# AC_DCConvertor_v2.net
KiCad netlist of a schematic drawn in Altium Designer
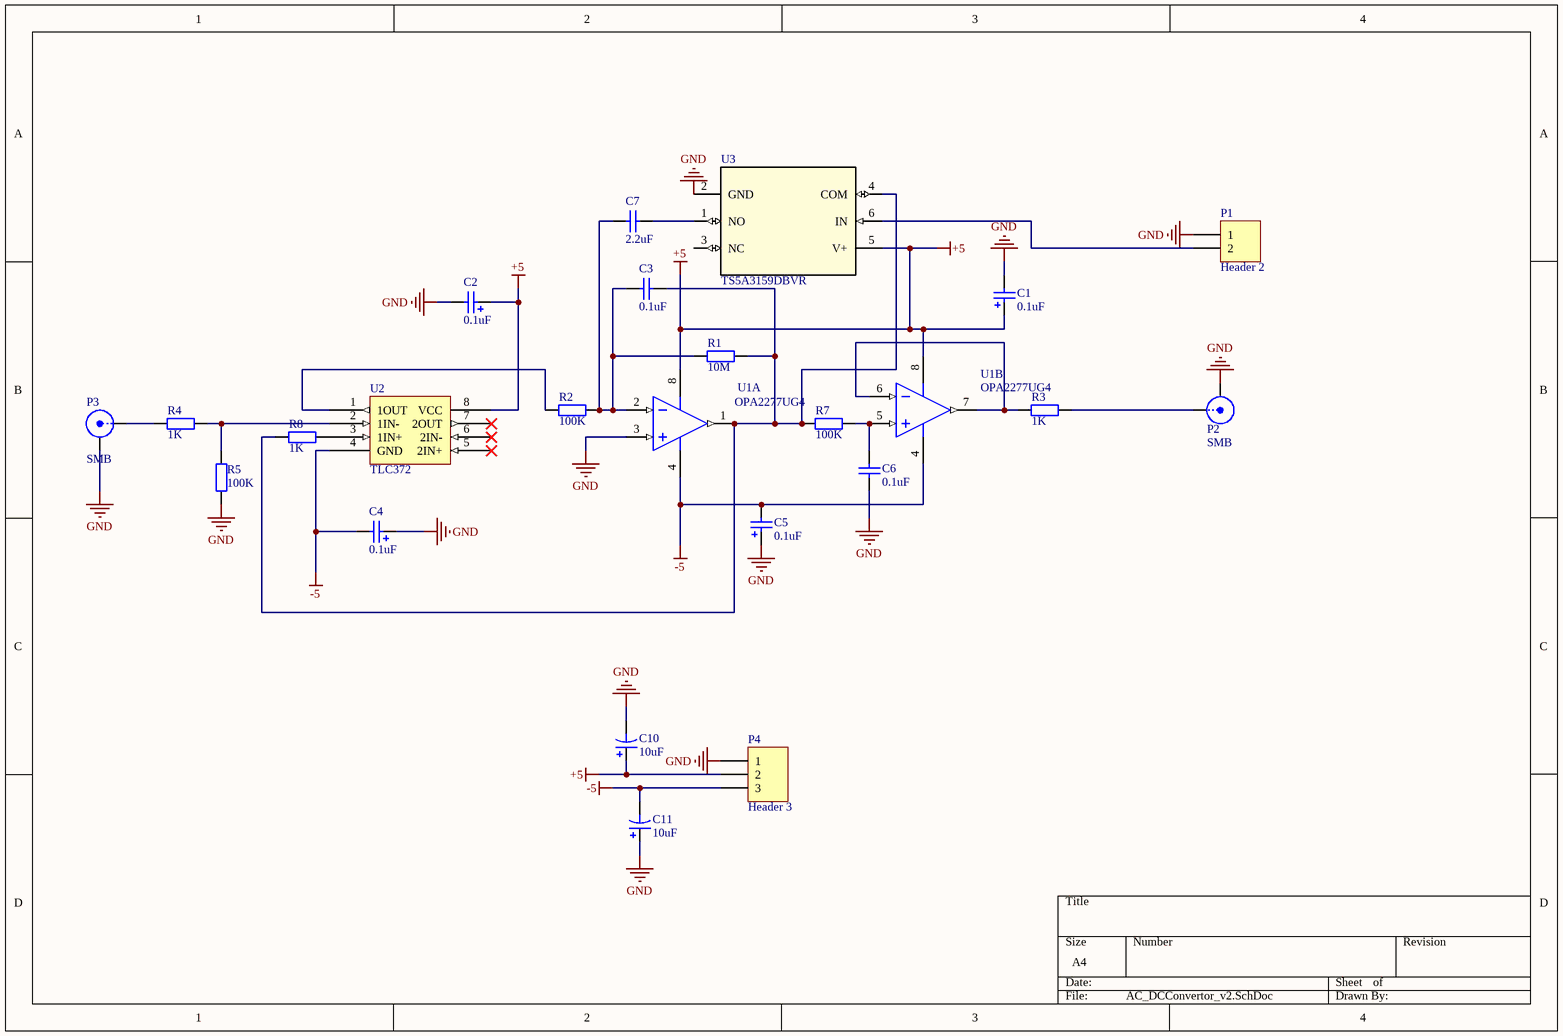
[diagram p0: AC_DCConvertor_v2.SchDoc]

(export (version "E")
  (design (tool "Eeschema 10.0.6"))
  (components
    (comp (ref "C1")
      (value "0.1uF")
      (footprint "C0805")
      (description "Polarized Capacitor (Axial)")
      (fields (field (name "Comment") "Cap Pol2") (field (name "PUBLISHER") "Altium Limited"))
      (libsource (lib "Miscellaneous Devices") (part "Cap Pol2"))
    )
    (comp (ref "C2")
      (value "0.1uF")
      (footprint "C0805")
      (description "Polarized Capacitor (Axial)")
      (fields (field (name "Comment") "Cap Pol2") (field (name "PUBLISHER") "Altium Limited"))
      (libsource (lib "Miscellaneous Devices") (part "Cap Pol2"))
    )
    (comp (ref "C3")
      (value "0.1uF")
      (footprint "C0805")
      (description "Capacitor (Semiconductor SIM Model)")
      (fields (field (name "Comment") "Cap Semi") (field (name "PUBLISHER") "Altium Limited"))
      (libsource (lib "Miscellaneous Devices") (part "Cap Semi"))
    )
    (comp (ref "C4")
      (value "0.1uF")
      (footprint "C0805")
      (description "Polarized Capacitor (Axial)")
      (fields (field (name "Comment") "Cap Pol2") (field (name "PUBLISHER") "Altium Limited"))
      (libsource (lib "Miscellaneous Devices") (part "Cap Pol2"))
    )
    (comp (ref "C5")
      (value "0.1uF")
      (footprint "C0805")
      (description "Polarized Capacitor (Axial)")
      (fields (field (name "Comment") "Cap Pol2") (field (name "PUBLISHER") "Altium Limited"))
      (libsource (lib "Miscellaneous Devices") (part "Cap Pol2"))
    )
    (comp (ref "C6")
      (value "0.1uF")
      (footprint "C0805")
      (description "Capacitor (Semiconductor SIM Model)")
      (fields (field (name "Comment") "Cap Semi") (field (name "PUBLISHER") "Altium Limited"))
      (libsource (lib "Miscellaneous Devices") (part "Cap Semi"))
    )
    (comp (ref "C7")
      (value "2.2uF")
      (footprint "C0805")
      (description "Capacitor (Semiconductor SIM Model)")
      (fields (field (name "Comment") "Cap Semi") (field (name "PUBLISHER") "Altium Limited"))
      (libsource (lib "Miscellaneous Devices") (part "Cap Semi"))
    )
    (comp (ref "C10")
      (value "10uF")
      (footprint "C0805")
      (description "Polarized Capacitor (Surface Mount)")
      (fields (field (name "Comment") "Cap Pol3") (field (name "PUBLISHER") "Altium Limited"))
      (libsource (lib "Miscellaneous Devices") (part "Cap Pol3"))
    )
    (comp (ref "C11")
      (value "10uF")
      (footprint "C0805")
      (description "Polarized Capacitor (Surface Mount)")
      (fields (field (name "Comment") "Cap Pol3") (field (name "PUBLISHER") "Altium Limited"))
      (libsource (lib "Miscellaneous Devices") (part "Cap Pol3"))
    )
    (comp (ref "P1")
      (value "Header 2")
      (footprint "HDR1X2")
      (description "Header, 2-Pin")
      (fields (field (name "PUBLISHER") "Altium Limited"))
      (libsource (lib "Miscellaneous Connectors") (part "Header 2"))
    )
    (comp (ref "P2")
      (value "SMB")
      (footprint "SMB_V-RJ45")
      (description "SMB Straight Connector")
      (fields (field (name "PUBLISHER") "Altium Limited"))
      (libsource (lib "Miscellaneous Connectors") (part "SMB"))
    )
    (comp (ref "P3")
      (value "SMB")
      (footprint "SMB_V-RJ45")
      (description "SMB Straight Connector")
      (fields (field (name "PUBLISHER") "Altium Limited"))
      (libsource (lib "Miscellaneous Connectors") (part "SMB"))
    )
    (comp (ref "P4")
      (value "Header 3")
      (footprint "HDR1X3")
      (description "Header, 3-Pin")
      (fields (field (name "PUBLISHER") "Altium Limited"))
      (libsource (lib "Miscellaneous Connectors") (part "Header 3"))
    )
    (comp (ref "R1")
      (value "10M")
      (footprint "C0805")
      (description "Resistor")
      (fields (field (name "Comment") "Res2") (field (name "PUBLISHER") "Altium Limited"))
      (libsource (lib "Miscellaneous Devices") (part "Res2"))
    )
    (comp (ref "R2")
      (value "100K")
      (footprint "C0805")
      (description "Resistor")
      (fields (field (name "Comment") "Res2") (field (name "PUBLISHER") "Altium Limited"))
      (libsource (lib "") (part "Res2_1"))
    )
    (comp (ref "R3")
      (value "1K")
      (footprint "C0805")
      (description "Resistor")
      (fields (field (name "Comment") "Res2") (field (name "PUBLISHER") "Altium Limited"))
      (libsource (lib "Miscellaneous Devices") (part "Res2"))
    )
    (comp (ref "R4")
      (value "1K")
      (footprint "C0805")
      (description "Resistor")
      (fields (field (name "Comment") "Res2") (field (name "PUBLISHER") "Altium Limited"))
      (libsource (lib "Miscellaneous Devices") (part "Res2"))
    )
    (comp (ref "R5")
      (value "100K")
      (footprint "C0805")
      (description "Resistor")
      (fields (field (name "Comment") "Res2") (field (name "PUBLISHER") "Altium Limited"))
      (libsource (lib "") (part "Res2_2"))
    )
    (comp (ref "R7")
      (value "100K")
      (footprint "C0805")
      (description "Resistor")
      (fields (field (name "Comment") "Res2") (field (name "PUBLISHER") "Altium Limited"))
      (libsource (lib "Miscellaneous Devices") (part "Res2"))
    )
    (comp (ref "R8")
      (value "1K")
      (footprint "C0805")
      (description "Resistor")
      (fields (field (name "Comment") "Res2") (field (name "PUBLISHER") "Altium Limited"))
      (libsource (lib "Miscellaneous Devices") (part "Res2"))
    )
    (comp (ref "U1")
      (value "OPA2277UG4")
      (footprint "TI-D8_M")
      (fields (field (name "MANUFACTURER") "Texas Instruments"))
      (libsource (lib "TI Amplifiers and Linear Operational Amplifier Precision Amplifier Part One") (part "OPA2277UG4"))
    )
    (comp (ref "U2") (value "TLC372") (footprint "SO8_M") (libsource (lib "TLC372") (part "TLC372")))
    (comp (ref "U3")
      (value "TS5A3159DBVR")
      (footprint "DBV0006A_N")
      (description "Imported")
      (fields
        (field (name "ALTERNATE PARTNUMBER") "TS5A3159DBVT")
        (field (name "MANUFACTURER") "Texas Instruments")
      )
      (libsource (lib "TS5A3159_SOT-32") (part "TS5A3159DBVR"))
    )
  )
  (nets
    (net (code "1") (name "+5") (class "Default")
      (node (ref "C1") (pin "1") (pinfunction "1_1") (pintype "passive"))
      (node (ref "C10") (pin "1") (pinfunction "1_1") (pintype "passive"))
      (node (ref "C2") (pin "1") (pinfunction "1_1") (pintype "passive"))
      (node (ref "P4") (pin "2") (pinfunction "2_2") (pintype "passive"))
      (node (ref "U1") (pin "8") (pinfunction "V+_8") (pintype "power_in"))
      (node (ref "U2") (pin "8") (pinfunction "VCC_8") (pintype "power_in"))
      (node (ref "U3") (pin "5") (pinfunction "V+_5") (pintype "power_in"))
    )
    (net (code "2") (name "-5") (class "Default")
      (node (ref "C11") (pin "2") (pinfunction "2_2") (pintype "passive"))
      (node (ref "C4") (pin "2") (pinfunction "2_2") (pintype "passive"))
      (node (ref "C5") (pin "2") (pinfunction "2_2") (pintype "passive"))
      (node (ref "P4") (pin "3") (pinfunction "3_3") (pintype "passive"))
      (node (ref "U1") (pin "4") (pinfunction "V-_4") (pintype "power_in"))
      (node (ref "U2") (pin "4") (pinfunction "GND_4") (pintype "power_in"))
    )
    (net (code "3") (name "GND") (class "Default")
      (node (ref "C1") (pin "2") (pinfunction "2_2") (pintype "passive"))
      (node (ref "C10") (pin "2") (pinfunction "2_2") (pintype "passive"))
      (node (ref "C11") (pin "1") (pinfunction "1_1") (pintype "passive"))
      (node (ref "C2") (pin "2") (pinfunction "2_2") (pintype "passive"))
      (node (ref "C4") (pin "1") (pinfunction "1_1") (pintype "passive"))
      (node (ref "C5") (pin "1") (pinfunction "1_1") (pintype "passive"))
      (node (ref "C6") (pin "2") (pinfunction "2_2") (pintype "passive"))
      (node (ref "P1") (pin "1") (pinfunction "1_1") (pintype "passive"))
      (node (ref "P2") (pin "2") (pinfunction "Y_2") (pintype "passive"))
      (node (ref "P3") (pin "2") (pinfunction "Y_2") (pintype "passive"))
      (node (ref "P4") (pin "1") (pinfunction "1_1") (pintype "passive"))
      (node (ref "R5") (pin "1") (pinfunction "1_1") (pintype "passive"))
      (node (ref "U1") (pin "3") (pinfunction "IN_A+_3") (pintype "input"))
      (node (ref "U3") (pin "2") (pinfunction "GND_2") (pintype "power_in"))
    )
    (net (code "4") (name "Net-(P2-X)") (class "Default")
      (node (ref "P2") (pin "1") (pinfunction "X_1") (pintype "passive"))
      (node (ref "R3") (pin "2") (pinfunction "2_2") (pintype "passive"))
    )
    (net (code "5") (name "Net-(P3-X)") (class "Default")
      (node (ref "P3") (pin "1") (pinfunction "X_1") (pintype "passive"))
      (node (ref "R4") (pin "1") (pinfunction "1_1") (pintype "passive"))
    )
    (net (code "6") (name "Net-(U1A-IN_A-)") (class "Default")
      (node (ref "C3") (pin "1") (pinfunction "1_1") (pintype "passive"))
      (node (ref "C7") (pin "1") (pinfunction "1_1") (pintype "passive"))
      (node (ref "R1") (pin "1") (pinfunction "1_1") (pintype "passive"))
      (node (ref "R2") (pin "1") (pinfunction "1_1") (pintype "passive"))
      (node (ref "U1") (pin "2") (pinfunction "IN_A-_2") (pintype "input"))
    )
    (net (code "7") (name "Net-(U1A-OUT_A)") (class "Default")
      (node (ref "C3") (pin "2") (pinfunction "2_2") (pintype "passive"))
      (node (ref "R1") (pin "2") (pinfunction "2_2") (pintype "passive"))
      (node (ref "R7") (pin "1") (pinfunction "1_1") (pintype "passive"))
      (node (ref "R8") (pin "1") (pinfunction "1_1") (pintype "passive"))
      (node (ref "U1") (pin "1") (pinfunction "OUT_A_1") (pintype "output"))
      (node (ref "U3") (pin "4") (pinfunction "COM_4") (pintype "bidirectional"))
    )
    (net (code "8") (name "Net-(U1B-IN_B+)") (class "Default")
      (node (ref "C6") (pin "1") (pinfunction "1_1") (pintype "passive"))
      (node (ref "R7") (pin "2") (pinfunction "2_2") (pintype "passive"))
      (node (ref "U1") (pin "5") (pinfunction "IN_B+_5") (pintype "input"))
    )
    (net (code "9") (name "Net-(U1B-IN_B-)") (class "Default")
      (node (ref "R3") (pin "1") (pinfunction "1_1") (pintype "passive"))
      (node (ref "U1") (pin "6") (pinfunction "IN_B-_6") (pintype "input"))
      (node (ref "U1") (pin "7") (pinfunction "OUT_B_7") (pintype "output"))
    )
    (net (code "10") (name "Net-(U2-1IN+)") (class "Default")
      (node (ref "R8") (pin "2") (pinfunction "2_2") (pintype "passive"))
      (node (ref "U2") (pin "3") (pinfunction "1IN+_3") (pintype "input"))
    )
    (net (code "11") (name "Net-(U2-1IN-)") (class "Default")
      (node (ref "R4") (pin "2") (pinfunction "2_2") (pintype "passive"))
      (node (ref "R5") (pin "2") (pinfunction "2_2") (pintype "passive"))
      (node (ref "U2") (pin "2") (pinfunction "1IN-_2") (pintype "input"))
    )
    (net (code "12") (name "Net-(U2-1OUT)") (class "Default")
      (node (ref "R2") (pin "2") (pinfunction "2_2") (pintype "passive"))
      (node (ref "U2") (pin "1") (pinfunction "1OUT_1") (pintype "output"))
    )
    (net (code "13") (name "Net-(U3-IN)") (class "Default")
      (node (ref "P1") (pin "2") (pinfunction "2_2") (pintype "passive"))
      (node (ref "U3") (pin "6") (pinfunction "IN_6") (pintype "input"))
    )
    (net (code "14") (name "Net-(U3-NO)") (class "Default")
      (node (ref "C7") (pin "2") (pinfunction "2_2") (pintype "passive"))
      (node (ref "U3") (pin "1") (pinfunction "NO_1") (pintype "bidirectional"))
    )
    (net (code "15") (name "unconnected-(U2-2IN+-Pad5)") (class "Default")
      (node (ref "U2") (pin "5") (pinfunction "2IN+_5") (pintype "input+no_connect"))
    )
    (net (code "16") (name "unconnected-(U2-2IN--Pad6)") (class "Default")
      (node (ref "U2") (pin "6") (pinfunction "2IN-_6") (pintype "input+no_connect"))
    )
    (net (code "17") (name "unconnected-(U2-2OUT-Pad7)") (class "Default")
      (node (ref "U2") (pin "7") (pinfunction "2OUT_7") (pintype "output+no_connect"))
    )
    (net (code "18") (name "unconnected-(U3-NC-Pad3)") (class "Default")
      (node (ref "U3") (pin "3") (pinfunction "NC_3") (pintype "bidirectional"))
    )
  )
)
